# domino4_IPB.net
KiCad netlist of a schematic drawn in EAGLE
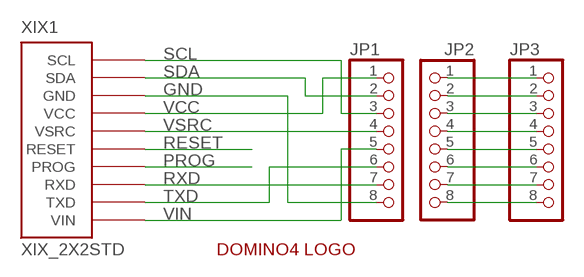
[diagram p0: schematic, sheet 1]

(export (version "E")
  (design (tool "Eeschema 10.0.6"))
  (components
    (comp (ref "JP1")
      (value "PINHD-1X8")
      (footprint "eagle-import:1X08")
      (libsource (lib "eagle-import") (part "PINHD-1X8"))
    )
    (comp (ref "JP2")
      (value "PINHD-1X8")
      (footprint "eagle-import:1X08")
      (libsource (lib "eagle-import") (part "PINHD-1X8"))
    )
    (comp (ref "JP3")
      (value "PINHD-1X8")
      (footprint "eagle-import:1X08")
      (libsource (lib "eagle-import") (part "PINHD-1X8"))
    )
    (comp (ref "U$1")
      (value "DOMINO4_LOGOHALF")
      (footprint "eagle-import:DOMINO4_LOGO_HALF")
      (libsource (lib "eagle-import") (part "DOMINO4_LOGOHALF"))
    )
    (comp (ref "XIX1")
      (value "XIX_2X2STD")
      (footprint "eagle-import:XIX_2X2")
      (libsource (lib "eagle-import") (part "XIX_2X2STD"))
    )
  )
  (nets
    (net (code "1") (name "/GND") (class "Default")
      (node (ref "JP1") (pin "8") (pinfunction "8_8") (pintype "passive"))
      (node (ref "XIX1") (pin "GND@1") (pinfunction "GND_GND@1") (pintype "power_in"))
      (node (ref "XIX1") (pin "GND@2") (pinfunction "GND_GND@2") (pintype "power_in"))
      (node (ref "XIX1") (pin "GND@3") (pinfunction "GND_GND@3") (pintype "power_in"))
      (node (ref "XIX1") (pin "GND@4") (pinfunction "GND_GND@4") (pintype "power_in"))
    )
    (net (code "2") (name "/PROG") (class "Default")
      (node (ref "XIX1") (pin "PROG@5") (pinfunction "PROG_PROG@5") (pintype "bidirectional"))
      (node (ref "XIX1") (pin "PROG@6") (pinfunction "PROG_PROG@6") (pintype "bidirectional"))
      (node (ref "XIX1") (pin "PROG@7") (pinfunction "PROG_PROG@7") (pintype "bidirectional"))
      (node (ref "XIX1") (pin "PROG@8") (pinfunction "PROG_PROG@8") (pintype "bidirectional"))
    )
    (net (code "3") (name "/RESET") (class "Default")
      (node (ref "XIX1") (pin "RESET@5") (pinfunction "RESET_RESET@5") (pintype "bidirectional"))
      (node (ref "XIX1") (pin "RESET@6") (pinfunction "RESET_RESET@6") (pintype "bidirectional"))
      (node (ref "XIX1") (pin "RESET@7") (pinfunction "RESET_RESET@7") (pintype "bidirectional"))
      (node (ref "XIX1") (pin "RESET@8") (pinfunction "RESET_RESET@8") (pintype "bidirectional"))
    )
    (net (code "4") (name "/RXD") (class "Default")
      (node (ref "JP1") (pin "7") (pinfunction "7_7") (pintype "passive"))
      (node (ref "XIX1") (pin "RXD@5") (pinfunction "RXD_RXD@5") (pintype "bidirectional"))
      (node (ref "XIX1") (pin "RXD@6") (pinfunction "RXD_RXD@6") (pintype "bidirectional"))
      (node (ref "XIX1") (pin "RXD@7") (pinfunction "RXD_RXD@7") (pintype "bidirectional"))
      (node (ref "XIX1") (pin "RXD@8") (pinfunction "RXD_RXD@8") (pintype "bidirectional"))
    )
    (net (code "5") (name "/SCL") (class "Default")
      (node (ref "JP1") (pin "3") (pinfunction "3_3") (pintype "passive"))
      (node (ref "XIX1") (pin "SCL@1") (pinfunction "SCL_SCL@1") (pintype "bidirectional"))
      (node (ref "XIX1") (pin "SCL@2") (pinfunction "SCL_SCL@2") (pintype "bidirectional"))
      (node (ref "XIX1") (pin "SCL@3") (pinfunction "SCL_SCL@3") (pintype "bidirectional"))
      (node (ref "XIX1") (pin "SCL@4") (pinfunction "SCL_SCL@4") (pintype "bidirectional"))
    )
    (net (code "6") (name "/SDA") (class "Default")
      (node (ref "JP1") (pin "2") (pinfunction "2_2") (pintype "passive"))
      (node (ref "XIX1") (pin "SDA@1") (pinfunction "SDA_SDA@1") (pintype "bidirectional"))
      (node (ref "XIX1") (pin "SDA@2") (pinfunction "SDA_SDA@2") (pintype "bidirectional"))
      (node (ref "XIX1") (pin "SDA@3") (pinfunction "SDA_SDA@3") (pintype "bidirectional"))
      (node (ref "XIX1") (pin "SDA@4") (pinfunction "SDA_SDA@4") (pintype "bidirectional"))
    )
    (net (code "7") (name "/TXD") (class "Default")
      (node (ref "JP1") (pin "6") (pinfunction "6_6") (pintype "passive"))
      (node (ref "XIX1") (pin "TXD@5") (pinfunction "TXD_TXD@5") (pintype "bidirectional"))
      (node (ref "XIX1") (pin "TXD@6") (pinfunction "TXD_TXD@6") (pintype "bidirectional"))
      (node (ref "XIX1") (pin "TXD@7") (pinfunction "TXD_TXD@7") (pintype "bidirectional"))
      (node (ref "XIX1") (pin "TXD@8") (pinfunction "TXD_TXD@8") (pintype "bidirectional"))
    )
    (net (code "8") (name "/VCC") (class "Default")
      (node (ref "JP1") (pin "1") (pinfunction "1_1") (pintype "passive"))
      (node (ref "XIX1") (pin "VCC@1") (pinfunction "VCC_VCC@1") (pintype "power_in"))
      (node (ref "XIX1") (pin "VCC@2") (pinfunction "VCC_VCC@2") (pintype "power_in"))
      (node (ref "XIX1") (pin "VCC@3") (pinfunction "VCC_VCC@3") (pintype "power_in"))
      (node (ref "XIX1") (pin "VCC@4") (pinfunction "VCC_VCC@4") (pintype "power_in"))
    )
    (net (code "9") (name "/VIN") (class "Default")
      (node (ref "JP1") (pin "5") (pinfunction "5_5") (pintype "passive"))
      (node (ref "XIX1") (pin "VIN@5") (pinfunction "VIN_VIN@5") (pintype "power_in"))
      (node (ref "XIX1") (pin "VIN@6") (pinfunction "VIN_VIN@6") (pintype "power_in"))
      (node (ref "XIX1") (pin "VIN@7") (pinfunction "VIN_VIN@7") (pintype "power_in"))
      (node (ref "XIX1") (pin "VIN@8") (pinfunction "VIN_VIN@8") (pintype "power_in"))
    )
    (net (code "10") (name "/VSRC") (class "Default")
      (node (ref "JP1") (pin "4") (pinfunction "4_4") (pintype "passive"))
      (node (ref "XIX1") (pin "VSRC@1") (pinfunction "VSRC_VSRC@1") (pintype "power_in"))
      (node (ref "XIX1") (pin "VSRC@2") (pinfunction "VSRC_VSRC@2") (pintype "power_in"))
      (node (ref "XIX1") (pin "VSRC@3") (pinfunction "VSRC_VSRC@3") (pintype "power_in"))
      (node (ref "XIX1") (pin "VSRC@4") (pinfunction "VSRC_VSRC@4") (pintype "power_in"))
    )
    (net (code "11") (name "Net-(JP2-Pad1)") (class "Default")
      (node (ref "JP2") (pin "1") (pinfunction "1_1") (pintype "passive"))
      (node (ref "JP3") (pin "1") (pinfunction "1_1") (pintype "passive"))
    )
    (net (code "12") (name "Net-(JP2-Pad2)") (class "Default")
      (node (ref "JP2") (pin "2") (pinfunction "2_2") (pintype "passive"))
      (node (ref "JP3") (pin "2") (pinfunction "2_2") (pintype "passive"))
    )
    (net (code "13") (name "Net-(JP2-Pad3)") (class "Default")
      (node (ref "JP2") (pin "3") (pinfunction "3_3") (pintype "passive"))
      (node (ref "JP3") (pin "3") (pinfunction "3_3") (pintype "passive"))
    )
    (net (code "14") (name "Net-(JP2-Pad4)") (class "Default")
      (node (ref "JP2") (pin "4") (pinfunction "4_4") (pintype "passive"))
      (node (ref "JP3") (pin "4") (pinfunction "4_4") (pintype "passive"))
    )
    (net (code "15") (name "Net-(JP2-Pad5)") (class "Default")
      (node (ref "JP2") (pin "5") (pinfunction "5_5") (pintype "passive"))
      (node (ref "JP3") (pin "5") (pinfunction "5_5") (pintype "passive"))
    )
    (net (code "16") (name "Net-(JP2-Pad6)") (class "Default")
      (node (ref "JP2") (pin "6") (pinfunction "6_6") (pintype "passive"))
      (node (ref "JP3") (pin "6") (pinfunction "6_6") (pintype "passive"))
    )
    (net (code "17") (name "Net-(JP2-Pad7)") (class "Default")
      (node (ref "JP2") (pin "7") (pinfunction "7_7") (pintype "passive"))
      (node (ref "JP3") (pin "7") (pinfunction "7_7") (pintype "passive"))
    )
    (net (code "18") (name "Net-(JP2-Pad8)") (class "Default")
      (node (ref "JP2") (pin "8") (pinfunction "8_8") (pintype "passive"))
      (node (ref "JP3") (pin "8") (pinfunction "8_8") (pintype "passive"))
    )
  )
)
